# ISPBreakout.net
KiCad netlist of a schematic drawn in EAGLE
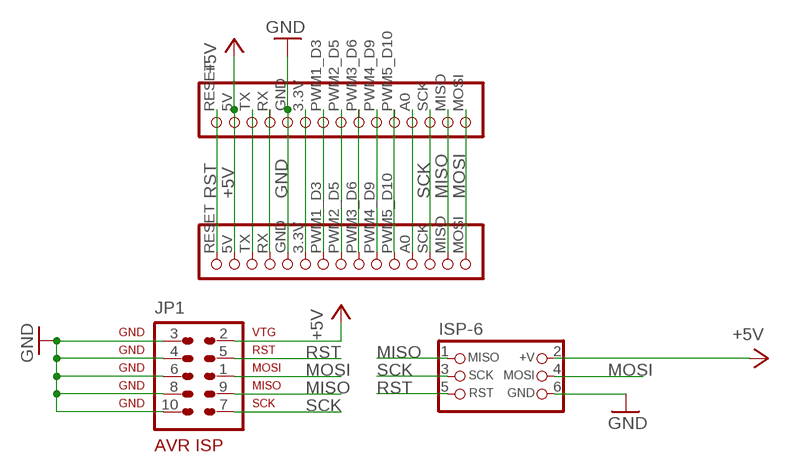
[diagram p0: schematic, sheet 1]

(export (version "E")
  (design (tool "Eeschema 10.0.6"))
  (components
    (comp (ref "ISP-6")
      (value "ISP 6")
      (footprint "eagle-import:HEADER_PRG_2X03")
      (libsource (lib "eagle-import") (part "CON_HEADER_PRG_AVR_ICSP-PTH"))
    )
    (comp (ref "JP1")
      (value "ISP-10")
      (footprint "eagle-import:AVR-ISP-10")
      (libsource (lib "eagle-import") (part "AVR-ISP-10"))
    )
    (comp (ref "U$1")
      (value "RF1_HEADER_LEFT")
      (footprint "eagle-import:RF1_LEFTHEADER_ONLY")
      (libsource (lib "eagle-import") (part "RF1_HEADER_LEFT"))
    )
    (comp (ref "U$2")
      (value "RF1_HEADER_LEFT")
      (footprint "eagle-import:RF1_LEFTHEADER_ONLY")
      (libsource (lib "eagle-import") (part "RF1_HEADER_LEFT"))
    )
  )
  (nets
    (net (code "1") (name "+5V") (class "Default")
      (node (ref "ISP-6") (pin "2") (pinfunction "+V_2") (pintype "passive"))
      (node (ref "JP1") (pin "2") (pinfunction "2_2") (pintype "passive"))
      (node (ref "U$1") (pin "5V") (pinfunction "5V_5V") (pintype "passive"))
      (node (ref "U$2") (pin "5V") (pinfunction "5V_5V") (pintype "passive"))
    )
    (net (code "2") (name "/MISO") (class "Default")
      (node (ref "ISP-6") (pin "1") (pinfunction "MISO_1") (pintype "passive"))
      (node (ref "JP1") (pin "9") (pinfunction "9_9") (pintype "passive"))
      (node (ref "U$1") (pin "MISO") (pinfunction "MISO_MISO") (pintype "passive"))
      (node (ref "U$2") (pin "MISO") (pinfunction "MISO_MISO") (pintype "passive"))
    )
    (net (code "3") (name "/MOSI") (class "Default")
      (node (ref "ISP-6") (pin "4") (pinfunction "MOSI_4") (pintype "passive"))
      (node (ref "JP1") (pin "1") (pinfunction "1_1") (pintype "passive"))
      (node (ref "U$1") (pin "MOSI") (pinfunction "MOSI_MOSI") (pintype "passive"))
      (node (ref "U$2") (pin "MOSI") (pinfunction "MOSI_MOSI") (pintype "passive"))
    )
    (net (code "4") (name "/RST") (class "Default")
      (node (ref "ISP-6") (pin "5") (pinfunction "RST_5") (pintype "passive"))
      (node (ref "JP1") (pin "5") (pinfunction "5_5") (pintype "passive"))
      (node (ref "U$1") (pin "RESET") (pinfunction "RESET_RESET") (pintype "passive"))
      (node (ref "U$2") (pin "RESET") (pinfunction "RESET_RESET") (pintype "passive"))
    )
    (net (code "5") (name "/SCK") (class "Default")
      (node (ref "ISP-6") (pin "3") (pinfunction "SCK_3") (pintype "passive"))
      (node (ref "JP1") (pin "7") (pinfunction "7_7") (pintype "passive"))
      (node (ref "U$1") (pin "SCK") (pinfunction "SCK_SCK") (pintype "passive"))
      (node (ref "U$2") (pin "SCK") (pinfunction "SCK_SCK") (pintype "passive"))
    )
    (net (code "6") (name "GND") (class "Default")
      (node (ref "ISP-6") (pin "6") (pinfunction "GND_6") (pintype "passive"))
      (node (ref "JP1") (pin "10") (pinfunction "10_10") (pintype "passive"))
      (node (ref "JP1") (pin "3") (pinfunction "3_3") (pintype "passive"))
      (node (ref "JP1") (pin "4") (pinfunction "4_4") (pintype "passive"))
      (node (ref "JP1") (pin "6") (pinfunction "6_6") (pintype "passive"))
      (node (ref "JP1") (pin "8") (pinfunction "8_8") (pintype "passive"))
      (node (ref "U$1") (pin "GND") (pinfunction "GND_GND") (pintype "passive"))
      (node (ref "U$2") (pin "GND") (pinfunction "GND_GND") (pintype "passive"))
    )
    (net (code "7") (name "Net-(U$1-PC0)") (class "Default")
      (node (ref "U$1") (pin "A0") (pinfunction "PC0_A0") (pintype "passive"))
      (node (ref "U$2") (pin "A0") (pinfunction "PC0_A0") (pintype "passive"))
    )
    (net (code "8") (name "Net-(U$1-PWM1)") (class "Default")
      (node (ref "U$1") (pin "PWM1_D3") (pinfunction "PWM1_PWM1_D3") (pintype "passive"))
      (node (ref "U$2") (pin "PWM1_D3") (pinfunction "PWM1_PWM1_D3") (pintype "passive"))
    )
    (net (code "9") (name "Net-(U$1-PWM2)") (class "Default")
      (node (ref "U$1") (pin "PWM2_D5") (pinfunction "PWM2_PWM2_D5") (pintype "passive"))
      (node (ref "U$2") (pin "PWM2_D5") (pinfunction "PWM2_PWM2_D5") (pintype "passive"))
    )
    (net (code "10") (name "Net-(U$1-PWM3)") (class "Default")
      (node (ref "U$1") (pin "PWM3_D6") (pinfunction "PWM3_PWM3_D6") (pintype "passive"))
      (node (ref "U$2") (pin "PWM3_D6") (pinfunction "PWM3_PWM3_D6") (pintype "passive"))
    )
    (net (code "11") (name "Net-(U$1-PWM4)") (class "Default")
      (node (ref "U$1") (pin "PWM4_D9") (pinfunction "PWM4_PWM4_D9") (pintype "passive"))
      (node (ref "U$2") (pin "PWM4_D9") (pinfunction "PWM4_PWM4_D9") (pintype "passive"))
    )
    (net (code "12") (name "Net-(U$1-PWM5)") (class "Default")
      (node (ref "U$1") (pin "PWM5_D10") (pinfunction "PWM5_PWM5_D10") (pintype "passive"))
      (node (ref "U$2") (pin "PWM5_D10") (pinfunction "PWM5_PWM5_D10") (pintype "passive"))
    )
    (net (code "13") (name "Net-(U$1-Pad3.3V)") (class "Default")
      (node (ref "U$1") (pin "3.3V") (pinfunction "3.3V_3.3V") (pintype "passive"))
      (node (ref "U$2") (pin "3.3V") (pinfunction "3.3V_3.3V") (pintype "passive"))
    )
    (net (code "14") (name "Net-(U$1-PadRX)") (class "Default")
      (node (ref "U$1") (pin "RX") (pinfunction "RX_RX") (pintype "passive"))
      (node (ref "U$2") (pin "RX") (pinfunction "RX_RX") (pintype "passive"))
    )
    (net (code "15") (name "Net-(U$1-PadTX)") (class "Default")
      (node (ref "U$1") (pin "TX") (pinfunction "TX_TX") (pintype "passive"))
      (node (ref "U$2") (pin "TX") (pinfunction "TX_TX") (pintype "passive"))
    )
  )
)
